# ai.net
KiCad netlist of a schematic drawn in Altium Designer
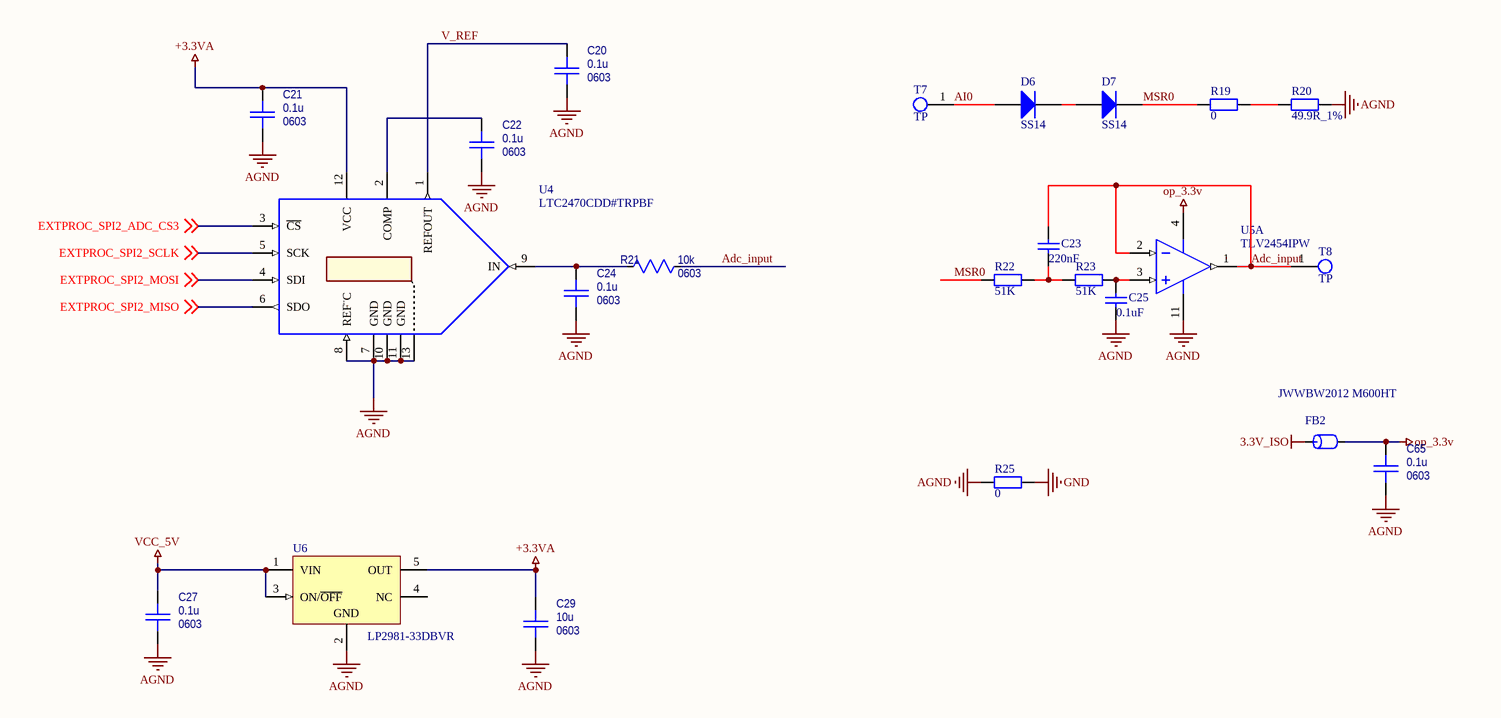
[diagram p0: ai.SchDoc]

(export (version "E")
  (design (tool "Eeschema 10.0.6"))
  (components
    (comp (ref "C20")
      (value "0.1u")
      (footprint "CAPC1608X092N_0603")
      (description "Capacitor, MLCC")
      (fields
        (field (name "PARTNUMBER") "C0603C104M5RACTU")
        (field (name "TOLERANCE") "[tol]")
        (field (name "PACKAGE") "0603")
      )
      (libsource (lib "Karl") (part "Capacitor_0603"))
    )
    (comp (ref "C21")
      (value "0.1u")
      (footprint "CAPC1608X092N_0603")
      (description "Capacitor, MLCC")
      (fields
        (field (name "PARTNUMBER") "C0603C104M5RACTU")
        (field (name "TOLERANCE") "[tol]")
        (field (name "PACKAGE") "0603")
      )
      (libsource (lib "Karl") (part "Capacitor_0603"))
    )
    (comp (ref "C22")
      (value "0.1u")
      (footprint "CAPC1608X092N_0603")
      (description "Capacitor, MLCC")
      (fields
        (field (name "PARTNUMBER") "C0603C104M5RACTU")
        (field (name "TOLERANCE") "[tol]")
        (field (name "PACKAGE") "0603")
      )
      (libsource (lib "Karl") (part "Capacitor_0603"))
    )
    (comp (ref "C23")
      (value "220nF")
      (footprint "0805C")
      (description "Capacitor")
      (fields (field (name "PUBLISHER") "Altium Limited"))
      (libsource (lib "Miscellaneous Devices") (part "Cap"))
    )
    (comp (ref "C24")
      (value "0.1u")
      (footprint "CAPC1608X092N_0603")
      (description "Capacitor, MLCC")
      (fields
        (field (name "PARTNUMBER") "C0603C104M5RACTU")
        (field (name "TOLERANCE") "[tol]")
        (field (name "PACKAGE") "0603")
      )
      (libsource (lib "Karl") (part "Capacitor_0603"))
    )
    (comp (ref "C25")
      (value "0.1uF")
      (footprint "0603C")
      (description "Capacitor")
      (fields (field (name "PUBLISHER") "Altium Limited"))
      (libsource (lib "Miscellaneous Devices") (part "Cap"))
    )
    (comp (ref "C27")
      (value "0.1u")
      (footprint "CAPC1608X092N_0603")
      (description "Capacitor, MLCC")
      (fields
        (field (name "PARTNUMBER") "C0603C104M5RACTU")
        (field (name "TOLERANCE") "[tol]")
        (field (name "PACKAGE") "0603")
      )
      (libsource (lib "Karl") (part "Capacitor_0603"))
    )
    (comp (ref "C29")
      (value "10u")
      (footprint "CAPC1608X092N_0603")
      (description "Capacitor, MLCC")
      (fields
        (field (name "PARTNUMBER") "GRM188R61A106KE69D")
        (field (name "TOLERANCE") "[tol]")
        (field (name "PACKAGE") "0603")
      )
      (libsource (lib "Karl") (part "Capacitor_0603"))
    )
    (comp (ref "C65")
      (value "0.1u")
      (footprint "CAPC1608X092N_0603")
      (description "Capacitor, MLCC")
      (fields
        (field (name "PARTNUMBER") "C0603C104M5RACTU")
        (field (name "TOLERANCE") "[tol]")
        (field (name "PACKAGE") "0603")
      )
      (libsource (lib "Karl") (part "Capacitor_0603"))
    )
    (comp (ref "D6")
      (value "SS14")
      (footprint "DO-214AC")
      (description "Default Diode")
      (fields (field (name "PUBLISHER") "Altium Limited"))
      (libsource (lib "Miscellaneous Devices") (part "Diode"))
    )
    (comp (ref "D7")
      (value "SS14")
      (footprint "DO-214AC")
      (description "Default Diode")
      (fields (field (name "PUBLISHER") "Altium Limited"))
      (libsource (lib "Miscellaneous Devices") (part "Diode"))
    )
    (comp (ref "FB2")
      (value "JWWBW2012 M600HT")
      (footprint "0805R")
      (libsource (lib "Schlib_20110825") (part "FB"))
    )
    (comp (ref "R19") (value "0") (footprint "0805R") (libsource (lib "MQlibrary") (part "Res0805M")))
    (comp (ref "R20") (value "49.9R_1%") (footprint "0805R") (libsource (lib "MQlibrary") (part "Res0805M")))
    (comp (ref "R21")
      (value "10k")
      (footprint "RESC1608X055N_0603")
      (description "Resistor, Standard")
      (fields
        (field (name "PARTNUMBER") "RR0816P-103-D")
        (field (name "TOLERANCE") "tol")
        (field (name "PACKAGE") "0603")
      )
      (libsource (lib "Karl") (part "Resistor_0603"))
    )
    (comp (ref "R22") (value "51K") (footprint "0603R") (libsource (lib "MQlibrary") (part "Res0805M")))
    (comp (ref "R23") (value "51K") (footprint "0603R") (libsource (lib "MQlibrary") (part "Res0805M")))
    (comp (ref "R25") (value "0") (footprint "1206R") (libsource (lib "MQlibrary") (part "Res0805M")))
    (comp (ref "T7") (value "TP") (footprint "TPD") (libsource (lib "Schlib_20110825") (part "TP")))
    (comp (ref "T8") (value "TP") (footprint "TPD") (libsource (lib "Schlib_20110825") (part "TP")))
    (comp (ref "U4")
      (value "LTC2470CDD#TRPBF")
      (footprint "LT-DD-12_V")
      (description "16-bit Analog-to-digital Converters, 12-pin SON (DD-12), 0 to 70 degC, Pb-Free, Tape and Reel")
      (libsource (lib "Bogen") (part "LTC2470CDD#TRPBF"))
    )
    (comp (ref "U5")
      (value "TLV2454IPW")
      (footprint "TSSOP14")
      (description "Quad High-speed, Ultra Low-power, Single-Supply TTL comparator")
      (fields (field (name "PUBLISHER") "Altium Limited"))
      (libsource (lib "Maxim Analog Comparator") (part "MAX908EPD"))
    )
    (comp (ref "U6")
      (value "LP2981-33DBVR")
      (footprint "DBV0005A_M")
      (description "Micropower 100 mA Ultra Low-Dropout Regulator, 5-pin SOT-23, Pb-Free")
      (libsource (lib "Bogen") (part "LP2981-33DBVR"))
    )
  )
  (nets
    (net (code "1") (name "+3.3VA") (class "Default")
      (node (ref "C21") (pin "1") (pinfunction "1_1") (pintype "passive"))
      (node (ref "C29") (pin "1") (pinfunction "1_1") (pintype "passive"))
      (node (ref "U4") (pin "12") (pinfunction "VCC_12") (pintype "power_in"))
      (node (ref "U6") (pin "5") (pinfunction "OUT_5") (pintype "power_in"))
    )
    (net (code "2") (name "/AI0") (class "Default")
      (node (ref "D6") (pin "1") (pinfunction "A_1") (pintype "passive"))
      (node (ref "T7") (pin "1") (pintype "passive"))
    )
    (net (code "3") (name "/Adc_input") (class "Default")
      (node (ref "C23") (pin "2") (pinfunction "2_2") (pintype "passive"))
      (node (ref "R21") (pin "1") (pinfunction "1_1") (pintype "passive"))
      (node (ref "T8") (pin "1") (pintype "passive"))
      (node (ref "U5") (pin "1") (pinfunction "OUT_1") (pintype "output"))
      (node (ref "U5") (pin "2") (pinfunction "IN-_2") (pintype "input"))
    )
    (net (code "4") (name "/MSR0") (class "Default")
      (node (ref "D7") (pin "2") (pinfunction "K_2") (pintype "passive"))
      (node (ref "R19") (pin "2") (pinfunction "2_2") (pintype "passive"))
      (node (ref "R22") (pin "2") (pinfunction "2_2") (pintype "passive"))
    )
    (net (code "5") (name "/V_REF") (class "Default")
      (node (ref "C20") (pin "1") (pinfunction "1_1") (pintype "passive"))
      (node (ref "U4") (pin "1") (pinfunction "REFOUT_1") (pintype "output"))
    )
    (net (code "6") (name "3.3V_ISO") (class "Default") (node (ref "FB2") (pin "1") (pintype "passive")))
    (net (code "7") (name "AGND") (class "Default")
      (node (ref "C20") (pin "2") (pinfunction "2_2") (pintype "passive"))
      (node (ref "C21") (pin "2") (pinfunction "2_2") (pintype "passive"))
      (node (ref "C22") (pin "2") (pinfunction "2_2") (pintype "passive"))
      (node (ref "C24") (pin "2") (pinfunction "2_2") (pintype "passive"))
      (node (ref "C25") (pin "1") (pinfunction "1_1") (pintype "passive"))
      (node (ref "C27") (pin "2") (pinfunction "2_2") (pintype "passive"))
      (node (ref "C29") (pin "2") (pinfunction "2_2") (pintype "passive"))
      (node (ref "C65") (pin "2") (pinfunction "2_2") (pintype "passive"))
      (node (ref "R20") (pin "1") (pinfunction "1_1") (pintype "passive"))
      (node (ref "R25") (pin "2") (pinfunction "2_2") (pintype "passive"))
      (node (ref "U4") (pin "10") (pinfunction "GND_10") (pintype "power_in"))
      (node (ref "U4") (pin "11") (pinfunction "GND_11") (pintype "power_in"))
      (node (ref "U4") (pin "13") (pinfunction "EP_13") (pintype "power_in"))
      (node (ref "U4") (pin "7") (pinfunction "GND_7") (pintype "power_in"))
      (node (ref "U4") (pin "8") (pinfunction "REF¨C_8") (pintype "input"))
      (node (ref "U5") (pin "11") (pinfunction "GND_11") (pintype "power_in"))
      (node (ref "U6") (pin "2") (pinfunction "GND_2") (pintype "power_in"))
    )
    (net (code "8") (name "EXTPROC_SPI2_ADC_CS3") (class "Default")
      (node (ref "U4") (pin "3") (pinfunction "~{CS}_3") (pintype "input"))
    )
    (net (code "9") (name "EXTPROC_SPI2_MISO") (class "Default")
      (node (ref "U4") (pin "6") (pinfunction "SDO_6") (pintype "output"))
    )
    (net (code "10") (name "EXTPROC_SPI2_MOSI") (class "Default")
      (node (ref "U4") (pin "4") (pinfunction "SDI_4") (pintype "input"))
    )
    (net (code "11") (name "EXTPROC_SPI2_SCLK") (class "Default")
      (node (ref "U4") (pin "5") (pinfunction "SCK_5") (pintype "input"))
    )
    (net (code "12") (name "GND") (class "Default")
      (node (ref "R25") (pin "1") (pinfunction "1_1") (pintype "passive"))
    )
    (net (code "13") (name "Net-(C23-Pad1)") (class "Default")
      (node (ref "C23") (pin "1") (pinfunction "1_1") (pintype "passive"))
      (node (ref "R22") (pin "1") (pinfunction "1_1") (pintype "passive"))
      (node (ref "R23") (pin "2") (pinfunction "2_2") (pintype "passive"))
    )
    (net (code "14") (name "Net-(D6-K)") (class "Default")
      (node (ref "D6") (pin "2") (pinfunction "K_2") (pintype "passive"))
      (node (ref "D7") (pin "1") (pinfunction "A_1") (pintype "passive"))
    )
    (net (code "15") (name "Net-(R19-Pad1)") (class "Default")
      (node (ref "R19") (pin "1") (pinfunction "1_1") (pintype "passive"))
      (node (ref "R20") (pin "2") (pinfunction "2_2") (pintype "passive"))
    )
    (net (code "16") (name "Net-(U4-COMP)") (class "Default")
      (node (ref "C22") (pin "1") (pinfunction "1_1") (pintype "passive"))
      (node (ref "U4") (pin "2") (pinfunction "COMP_2") (pintype "passive"))
    )
    (net (code "17") (name "Net-(U4-IN)") (class "Default")
      (node (ref "C24") (pin "1") (pinfunction "1_1") (pintype "passive"))
      (node (ref "R21") (pin "2") (pinfunction "2_2") (pintype "passive"))
      (node (ref "U4") (pin "9") (pinfunction "IN_9") (pintype "input"))
    )
    (net (code "18") (name "Net-(U5A-IN+)") (class "Default")
      (node (ref "C25") (pin "2") (pinfunction "2_2") (pintype "passive"))
      (node (ref "R23") (pin "1") (pinfunction "1_1") (pintype "passive"))
      (node (ref "U5") (pin "3") (pinfunction "IN+_3") (pintype "input"))
    )
    (net (code "19") (name "VCC_5V") (class "Default")
      (node (ref "C27") (pin "1") (pinfunction "1_1") (pintype "passive"))
      (node (ref "U6") (pin "1") (pinfunction "VIN_1") (pintype "power_in"))
      (node (ref "U6") (pin "3") (pinfunction "ON/~{OFF}_3") (pintype "input"))
    )
    (net (code "20") (name "op_3.3v") (class "Default")
      (node (ref "C65") (pin "1") (pinfunction "1_1") (pintype "passive"))
      (node (ref "FB2") (pin "2") (pintype "passive"))
      (node (ref "U5") (pin "4") (pinfunction "V+_4") (pintype "power_in"))
    )
    (net (code "21") (name "unconnected-(U6-NC-Pad4)") (class "Default")
      (node (ref "U6") (pin "4") (pinfunction "NC_4") (pintype "passive"))
    )
  )
)
